# Mock_HASP_Flight_Computer.net
KiCad netlist of a schematic drawn in EAGLE
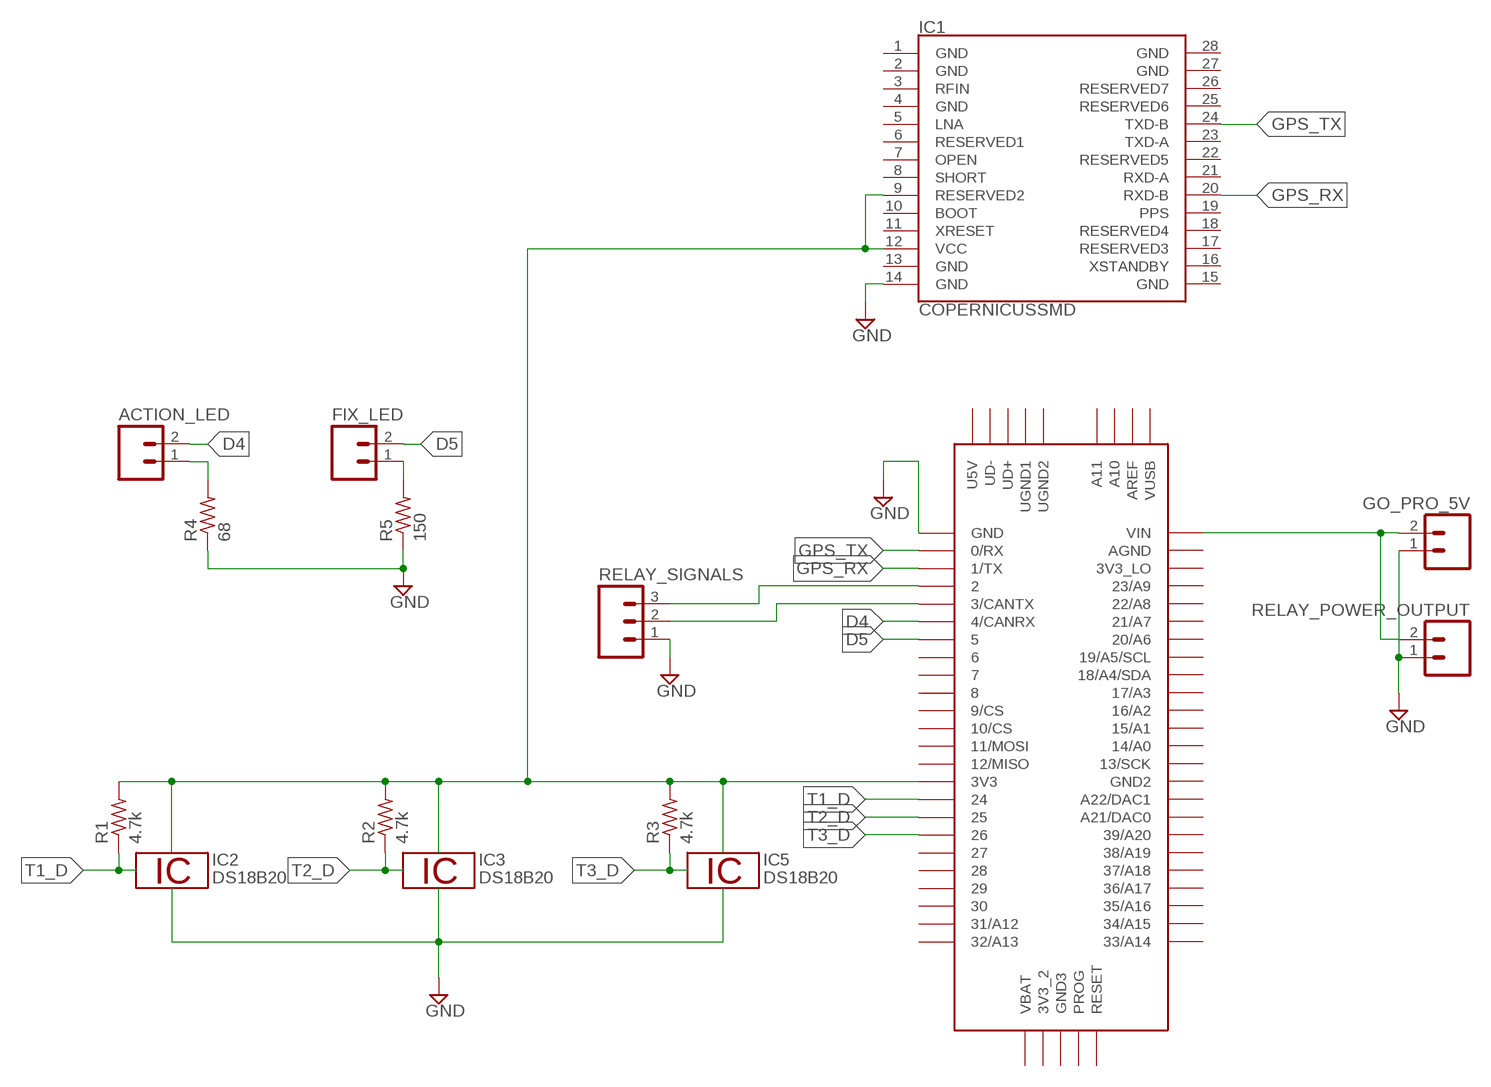
[diagram p0: schematic, sheet 1]

(export (version "E")
  (design (tool "Eeschema 10.0.6"))
  (components
    (comp (ref "ACTION_LED")
      (value "M02")
      (footprint "eagle-import:02P")
      (libsource (lib "eagle-import") (part "M02"))
    )
    (comp (ref "FIX_LED")
      (value "M02")
      (footprint "eagle-import:02P")
      (libsource (lib "eagle-import") (part "M02"))
    )
    (comp (ref "GO_PRO_5V")
      (value "M02")
      (footprint "eagle-import:02P")
      (libsource (lib "eagle-import") (part "M02"))
    )
    (comp (ref "IC1")
      (value "COPERNICUSSMD")
      (footprint "eagle-import:COPERNICUS")
      (libsource (lib "eagle-import") (part "COPERNICUSSMD"))
    )
    (comp (ref "IC2")
      (value "DS18B20")
      (footprint "eagle-import:TO92-")
      (libsource (lib "eagle-import") (part "DS18B20"))
    )
    (comp (ref "IC3")
      (value "DS18B20")
      (footprint "eagle-import:TO92-")
      (libsource (lib "eagle-import") (part "DS18B20"))
    )
    (comp (ref "IC5")
      (value "DS18B20")
      (footprint "eagle-import:TO92-")
      (libsource (lib "eagle-import") (part "DS18B20"))
    )
    (comp (ref "R1")
      (value "4.7k")
      (footprint "eagle-import:0207_10")
      (libsource (lib "eagle-import") (part "R-US_0207/10"))
    )
    (comp (ref "R2")
      (value "4.7k")
      (footprint "eagle-import:0207_10")
      (libsource (lib "eagle-import") (part "R-US_0207/10"))
    )
    (comp (ref "R3")
      (value "4.7k")
      (footprint "eagle-import:0207_10")
      (libsource (lib "eagle-import") (part "R-US_0207/10"))
    )
    (comp (ref "R4")
      (value "68")
      (footprint "eagle-import:0207_10")
      (libsource (lib "eagle-import") (part "R-US_0207/10"))
    )
    (comp (ref "R5")
      (value "150")
      (footprint "eagle-import:0207_10")
      (libsource (lib "eagle-import") (part "R-US_0207/10"))
    )
    (comp (ref "RELAY_POWER_OUTPUT")
      (value "M02")
      (footprint "eagle-import:02P")
      (libsource (lib "eagle-import") (part "M02"))
    )
    (comp (ref "RELAY_SIGNALS")
      (value "M03")
      (footprint "eagle-import:03P")
      (libsource (lib "eagle-import") (part "M03"))
    )
    (comp (ref "U$1")
      (value "TEENSY_3.5/3.6")
      (footprint "eagle-import:TEENSY_3.5_3.6")
      (libsource (lib "eagle-import") (part "TEENSY_3.5/3.6"))
    )
  )
  (nets
    (net (code "1") (name "D4") (class "Default")
      (node (ref "ACTION_LED") (pin "2") (pinfunction "2_2") (pintype "passive"))
      (node (ref "U$1") (pin "4/CANRX") (pinfunction "4/CANRX_4/CANRX") (pintype "bidirectional"))
    )
    (net (code "2") (name "D5") (class "Default")
      (node (ref "FIX_LED") (pin "2") (pinfunction "2_2") (pintype "passive"))
      (node (ref "U$1") (pin "5") (pinfunction "5_5") (pintype "bidirectional"))
    )
    (net (code "3") (name "GND") (class "Default")
      (node (ref "GO_PRO_5V") (pin "1") (pinfunction "1_1") (pintype "passive"))
      (node (ref "IC1") (pin "14") (pinfunction "GND_14") (pintype "bidirectional"))
      (node (ref "R4") (pin "1") (pinfunction "1_1") (pintype "passive"))
      (node (ref "R5") (pin "1") (pinfunction "1_1") (pintype "passive"))
      (node (ref "RELAY_POWER_OUTPUT") (pin "1") (pinfunction "1_1") (pintype "passive"))
      (node (ref "RELAY_SIGNALS") (pin "1") (pinfunction "1_1") (pintype "passive"))
      (node (ref "U$1") (pin "GND") (pinfunction "GND_GND") (pintype "bidirectional"))
    )
    (net (code "4") (name "GPS_RX") (class "Default")
      (node (ref "IC1") (pin "20") (pinfunction "RXD-B_20") (pintype "bidirectional"))
      (node (ref "U$1") (pin "1/TX") (pinfunction "1/TX_1/TX") (pintype "bidirectional"))
    )
    (net (code "5") (name "GPS_TX") (class "Default")
      (node (ref "IC1") (pin "24") (pinfunction "TXD-B_24") (pintype "bidirectional"))
      (node (ref "U$1") (pin "0/RX") (pinfunction "0/RX_0/RX") (pintype "bidirectional"))
    )
    (net (code "6") (name "Net-(ACTION_LED-Pad1)") (class "Default")
      (node (ref "ACTION_LED") (pin "1") (pinfunction "1_1") (pintype "passive"))
      (node (ref "R4") (pin "2") (pinfunction "2_2") (pintype "passive"))
    )
    (net (code "7") (name "Net-(FIX_LED-Pad1)") (class "Default")
      (node (ref "FIX_LED") (pin "1") (pinfunction "1_1") (pintype "passive"))
      (node (ref "R5") (pin "2") (pinfunction "2_2") (pintype "passive"))
    )
    (net (code "8") (name "Net-(GO_PRO_5V-Pad2)") (class "Default")
      (node (ref "GO_PRO_5V") (pin "2") (pinfunction "2_2") (pintype "passive"))
      (node (ref "RELAY_POWER_OUTPUT") (pin "2") (pinfunction "2_2") (pintype "passive"))
      (node (ref "U$1") (pin "VIN") (pinfunction "VIN_VIN") (pintype "bidirectional"))
    )
    (net (code "9") (name "Net-(IC1-RESERVED2)") (class "Default")
      (node (ref "IC1") (pin "12") (pinfunction "VCC_12") (pintype "bidirectional"))
      (node (ref "IC1") (pin "9") (pinfunction "RESERVED2_9") (pintype "bidirectional"))
      (node (ref "R1") (pin "2") (pinfunction "2_2") (pintype "passive"))
      (node (ref "R2") (pin "2") (pinfunction "2_2") (pintype "passive"))
      (node (ref "R3") (pin "2") (pinfunction "2_2") (pintype "passive"))
      (node (ref "U$1") (pin "3V3") (pinfunction "3V3_3V3") (pintype "bidirectional"))
    )
    (net (code "10") (name "Net-(RELAY_SIGNALS-Pad2)") (class "Default")
      (node (ref "RELAY_SIGNALS") (pin "2") (pinfunction "2_2") (pintype "passive"))
      (node (ref "U$1") (pin "3/CANTX") (pinfunction "3/CANTX_3/CANTX") (pintype "bidirectional"))
    )
    (net (code "11") (name "Net-(RELAY_SIGNALS-Pad3)") (class "Default")
      (node (ref "RELAY_SIGNALS") (pin "3") (pinfunction "3_3") (pintype "passive"))
      (node (ref "U$1") (pin "2") (pinfunction "2_2") (pintype "bidirectional"))
    )
    (net (code "12") (name "T1_D") (class "Default")
      (node (ref "R1") (pin "1") (pinfunction "1_1") (pintype "passive"))
      (node (ref "U$1") (pin "24") (pinfunction "24_24") (pintype "bidirectional"))
    )
    (net (code "13") (name "T2_D") (class "Default")
      (node (ref "R2") (pin "1") (pinfunction "1_1") (pintype "passive"))
      (node (ref "U$1") (pin "25") (pinfunction "25_25") (pintype "bidirectional"))
    )
    (net (code "14") (name "T3_D") (class "Default")
      (node (ref "R3") (pin "1") (pinfunction "1_1") (pintype "passive"))
      (node (ref "U$1") (pin "26") (pinfunction "26_26") (pintype "bidirectional"))
    )
    (net (code "15") (name "unconnected-(IC1-BOOT-Pad10)") (class "Default")
      (node (ref "IC1") (pin "10") (pinfunction "BOOT_10") (pintype "bidirectional"))
    )
    (net (code "16") (name "unconnected-(IC1-GND-Pad1)") (class "Default")
      (node (ref "IC1") (pin "1") (pinfunction "GND_1") (pintype "bidirectional"))
    )
    (net (code "17") (name "unconnected-(IC1-GND-Pad2)") (class "Default")
      (node (ref "IC1") (pin "2") (pinfunction "GND_2") (pintype "bidirectional"))
    )
    (net (code "18") (name "unconnected-(IC1-GND-Pad4)") (class "Default")
      (node (ref "IC1") (pin "4") (pinfunction "GND_4") (pintype "bidirectional"))
    )
    (net (code "19") (name "unconnected-(IC1-GND-Pad13)") (class "Default")
      (node (ref "IC1") (pin "13") (pinfunction "GND_13") (pintype "bidirectional"))
    )
    (net (code "20") (name "unconnected-(IC1-GND-Pad15)") (class "Default")
      (node (ref "IC1") (pin "15") (pinfunction "GND_15") (pintype "bidirectional"))
    )
    (net (code "21") (name "unconnected-(IC1-GND-Pad27)") (class "Default")
      (node (ref "IC1") (pin "27") (pinfunction "GND_27") (pintype "bidirectional"))
    )
    (net (code "22") (name "unconnected-(IC1-GND-Pad28)") (class "Default")
      (node (ref "IC1") (pin "28") (pinfunction "GND_28") (pintype "bidirectional"))
    )
    (net (code "23") (name "unconnected-(IC1-LNA-Pad5)") (class "Default")
      (node (ref "IC1") (pin "5") (pinfunction "LNA_5") (pintype "bidirectional"))
    )
    (net (code "24") (name "unconnected-(IC1-OPEN-Pad7)") (class "Default")
      (node (ref "IC1") (pin "7") (pinfunction "OPEN_7") (pintype "bidirectional"))
    )
    (net (code "25") (name "unconnected-(IC1-PPS-Pad19)") (class "Default")
      (node (ref "IC1") (pin "19") (pinfunction "PPS_19") (pintype "bidirectional"))
    )
    (net (code "26") (name "unconnected-(IC1-RESERVED1-Pad6)") (class "Default")
      (node (ref "IC1") (pin "6") (pinfunction "RESERVED1_6") (pintype "bidirectional"))
    )
    (net (code "27") (name "unconnected-(IC1-RESERVED3-Pad17)") (class "Default")
      (node (ref "IC1") (pin "17") (pinfunction "RESERVED3_17") (pintype "bidirectional"))
    )
    (net (code "28") (name "unconnected-(IC1-RESERVED4-Pad18)") (class "Default")
      (node (ref "IC1") (pin "18") (pinfunction "RESERVED4_18") (pintype "bidirectional"))
    )
    (net (code "29") (name "unconnected-(IC1-RESERVED5-Pad22)") (class "Default")
      (node (ref "IC1") (pin "22") (pinfunction "RESERVED5_22") (pintype "bidirectional"))
    )
    (net (code "30") (name "unconnected-(IC1-RESERVED6-Pad25)") (class "Default")
      (node (ref "IC1") (pin "25") (pinfunction "RESERVED6_25") (pintype "bidirectional"))
    )
    (net (code "31") (name "unconnected-(IC1-RESERVED7-Pad26)") (class "Default")
      (node (ref "IC1") (pin "26") (pinfunction "RESERVED7_26") (pintype "bidirectional"))
    )
    (net (code "32") (name "unconnected-(IC1-RFIN-Pad3)") (class "Default")
      (node (ref "IC1") (pin "3") (pinfunction "RFIN_3") (pintype "bidirectional"))
    )
    (net (code "33") (name "unconnected-(IC1-RXD-A-Pad21)") (class "Default")
      (node (ref "IC1") (pin "21") (pinfunction "RXD-A_21") (pintype "bidirectional"))
    )
    (net (code "34") (name "unconnected-(IC1-SHORT-Pad8)") (class "Default")
      (node (ref "IC1") (pin "8") (pinfunction "SHORT_8") (pintype "bidirectional"))
    )
    (net (code "35") (name "unconnected-(IC1-TXD-A-Pad23)") (class "Default")
      (node (ref "IC1") (pin "23") (pinfunction "TXD-A_23") (pintype "bidirectional"))
    )
    (net (code "36") (name "unconnected-(IC1-XRESET-Pad11)") (class "Default")
      (node (ref "IC1") (pin "11") (pinfunction "XRESET_11") (pintype "bidirectional"))
    )
    (net (code "37") (name "unconnected-(IC1-XSTANDBY-Pad16)") (class "Default")
      (node (ref "IC1") (pin "16") (pinfunction "XSTANDBY_16") (pintype "bidirectional"))
    )
    (net (code "38") (name "unconnected-(U$1-A21{slash}DAC0-Pad21{slash}DAC0)") (class "Default")
      (node (ref "U$1") (pin "21/DAC0") (pinfunction "A21/DAC0_21/DAC0") (pintype "bidirectional"))
    )
    (net (code "39") (name "unconnected-(U$1-Pad3V3_2)") (class "Default")
      (node (ref "U$1") (pin "3V3_2") (pinfunction "3V3_2_3V3_2") (pintype "bidirectional"))
    )
    (net (code "40") (name "unconnected-(U$1-Pad3V3_LO)") (class "Default")
      (node (ref "U$1") (pin "3V3_LO") (pinfunction "3V3_LO_3V3_LO") (pintype "bidirectional"))
    )
    (net (code "41") (name "unconnected-(U$1-Pad6)") (class "Default")
      (node (ref "U$1") (pin "6") (pinfunction "6_6") (pintype "bidirectional"))
    )
    (net (code "42") (name "unconnected-(U$1-Pad7)") (class "Default")
      (node (ref "U$1") (pin "7") (pinfunction "7_7") (pintype "bidirectional"))
    )
    (net (code "43") (name "unconnected-(U$1-Pad8)") (class "Default")
      (node (ref "U$1") (pin "8") (pinfunction "8_8") (pintype "bidirectional"))
    )
    (net (code "44") (name "unconnected-(U$1-Pad9{slash}CS)") (class "Default")
      (node (ref "U$1") (pin "9/CS") (pinfunction "9/CS_9/CS") (pintype "bidirectional"))
    )
    (net (code "45") (name "unconnected-(U$1-Pad10{slash}CS)") (class "Default")
      (node (ref "U$1") (pin "10/CS") (pinfunction "10/CS_10/CS") (pintype "bidirectional"))
    )
    (net (code "46") (name "unconnected-(U$1-Pad11{slash}MOSI)") (class "Default")
      (node (ref "U$1") (pin "11/MOSI") (pinfunction "11/MOSI_11/MOSI") (pintype "bidirectional"))
    )
    (net (code "47") (name "unconnected-(U$1-Pad12{slash}MISO)") (class "Default")
      (node (ref "U$1") (pin "12/MISO") (pinfunction "12/MISO_12/MISO") (pintype "bidirectional"))
    )
    (net (code "48") (name "unconnected-(U$1-Pad13{slash}SCK)") (class "Default")
      (node (ref "U$1") (pin "13/SCK") (pinfunction "13/SCK_13/SCK") (pintype "bidirectional"))
    )
    (net (code "49") (name "unconnected-(U$1-Pad14{slash}A0)") (class "Default")
      (node (ref "U$1") (pin "14/A0") (pinfunction "14/A0_14/A0") (pintype "bidirectional"))
    )
    (net (code "50") (name "unconnected-(U$1-Pad15{slash}A1)") (class "Default")
      (node (ref "U$1") (pin "15/A1") (pinfunction "15/A1_15/A1") (pintype "bidirectional"))
    )
    (net (code "51") (name "unconnected-(U$1-Pad16{slash}A2)") (class "Default")
      (node (ref "U$1") (pin "16/A2") (pinfunction "16/A2_16/A2") (pintype "bidirectional"))
    )
    (net (code "52") (name "unconnected-(U$1-Pad17{slash}A3)") (class "Default")
      (node (ref "U$1") (pin "17/A3") (pinfunction "17/A3_17/A3") (pintype "bidirectional"))
    )
    (net (code "53") (name "unconnected-(U$1-Pad18{slash}A4{slash}SDA)") (class "Default")
      (node (ref "U$1") (pin "18/A4/SDA") (pinfunction "18/A4/SDA_18/A4/SDA") (pintype "bidirectional"))
    )
    (net (code "54") (name "unconnected-(U$1-Pad19{slash}A5{slash}SCL)") (class "Default")
      (node (ref "U$1") (pin "19/A5/SCL") (pinfunction "19/A5/SCL_19/A5/SCL") (pintype "bidirectional"))
    )
    (net (code "55") (name "unconnected-(U$1-Pad20{slash}A6)") (class "Default")
      (node (ref "U$1") (pin "20/A6") (pinfunction "20/A6_20/A6") (pintype "bidirectional"))
    )
    (net (code "56") (name "unconnected-(U$1-Pad21{slash}A7)") (class "Default")
      (node (ref "U$1") (pin "21/A7") (pinfunction "21/A7_21/A7") (pintype "bidirectional"))
    )
    (net (code "57") (name "unconnected-(U$1-Pad22{slash}A8)") (class "Default")
      (node (ref "U$1") (pin "22/A8") (pinfunction "22/A8_22/A8") (pintype "bidirectional"))
    )
    (net (code "58") (name "unconnected-(U$1-Pad23{slash}A9)") (class "Default")
      (node (ref "U$1") (pin "23/A9") (pinfunction "23/A9_23/A9") (pintype "bidirectional"))
    )
    (net (code "59") (name "unconnected-(U$1-Pad27)") (class "Default")
      (node (ref "U$1") (pin "27") (pinfunction "27_27") (pintype "bidirectional"))
    )
    (net (code "60") (name "unconnected-(U$1-Pad28)") (class "Default")
      (node (ref "U$1") (pin "28") (pinfunction "28_28") (pintype "bidirectional"))
    )
    (net (code "61") (name "unconnected-(U$1-Pad29)") (class "Default")
      (node (ref "U$1") (pin "29") (pinfunction "29_29") (pintype "bidirectional"))
    )
    (net (code "62") (name "unconnected-(U$1-Pad30)") (class "Default")
      (node (ref "U$1") (pin "30") (pinfunction "30_30") (pintype "bidirectional"))
    )
    (net (code "63") (name "unconnected-(U$1-Pad31{slash}A12)") (class "Default")
      (node (ref "U$1") (pin "31/A12") (pinfunction "31/A12_31/A12") (pintype "bidirectional"))
    )
    (net (code "64") (name "unconnected-(U$1-Pad32{slash}A13)") (class "Default")
      (node (ref "U$1") (pin "32/A13") (pinfunction "32/A13_32/A13") (pintype "bidirectional"))
    )
    (net (code "65") (name "unconnected-(U$1-Pad33{slash}A14)") (class "Default")
      (node (ref "U$1") (pin "33/A14") (pinfunction "33/A14_33/A14") (pintype "bidirectional"))
    )
    (net (code "66") (name "unconnected-(U$1-Pad34{slash}A15)") (class "Default")
      (node (ref "U$1") (pin "34/A15") (pinfunction "34/A15_34/A15") (pintype "bidirectional"))
    )
    (net (code "67") (name "unconnected-(U$1-Pad35{slash}A16)") (class "Default")
      (node (ref "U$1") (pin "35/A16") (pinfunction "35/A16_35/A16") (pintype "bidirectional"))
    )
    (net (code "68") (name "unconnected-(U$1-Pad36{slash}A17)") (class "Default")
      (node (ref "U$1") (pin "36/A17") (pinfunction "36/A17_36/A17") (pintype "bidirectional"))
    )
    (net (code "69") (name "unconnected-(U$1-Pad37{slash}A18)") (class "Default")
      (node (ref "U$1") (pin "37/A18") (pinfunction "37/A18_37/A18") (pintype "bidirectional"))
    )
    (net (code "70") (name "unconnected-(U$1-Pad38{slash}A19)") (class "Default")
      (node (ref "U$1") (pin "38/A19") (pinfunction "38/A19_38/A19") (pintype "bidirectional"))
    )
    (net (code "71") (name "unconnected-(U$1-Pad39{slash}A20)") (class "Default")
      (node (ref "U$1") (pin "39/A20") (pinfunction "39/A20_39/A20") (pintype "bidirectional"))
    )
    (net (code "72") (name "unconnected-(U$1-PadA10)") (class "Default")
      (node (ref "U$1") (pin "A10") (pinfunction "A10_A10") (pintype "bidirectional"))
    )
    (net (code "73") (name "unconnected-(U$1-PadA11)") (class "Default")
      (node (ref "U$1") (pin "A11") (pinfunction "A11_A11") (pintype "bidirectional"))
    )
    (net (code "74") (name "unconnected-(U$1-PadA22{slash}DAC1)") (class "Default")
      (node (ref "U$1") (pin "A22/DAC1") (pinfunction "A22/DAC1_A22/DAC1") (pintype "bidirectional"))
    )
    (net (code "75") (name "unconnected-(U$1-PadAGND)") (class "Default")
      (node (ref "U$1") (pin "AGND") (pinfunction "AGND_AGND") (pintype "bidirectional"))
    )
    (net (code "76") (name "unconnected-(U$1-PadAREF)") (class "Default")
      (node (ref "U$1") (pin "AREF") (pinfunction "AREF_AREF") (pintype "bidirectional"))
    )
    (net (code "77") (name "unconnected-(U$1-PadGND2)") (class "Default")
      (node (ref "U$1") (pin "GND2") (pinfunction "GND2_GND2") (pintype "bidirectional"))
    )
    (net (code "78") (name "unconnected-(U$1-PadGND3)") (class "Default")
      (node (ref "U$1") (pin "GND3") (pinfunction "GND3_GND3") (pintype "bidirectional"))
    )
    (net (code "79") (name "unconnected-(U$1-PadPROG)") (class "Default")
      (node (ref "U$1") (pin "PROG") (pinfunction "PROG_PROG") (pintype "bidirectional"))
    )
    (net (code "80") (name "unconnected-(U$1-PadRESET)") (class "Default")
      (node (ref "U$1") (pin "RESET") (pinfunction "RESET_RESET") (pintype "bidirectional"))
    )
    (net (code "81") (name "unconnected-(U$1-PadU5V)") (class "Default")
      (node (ref "U$1") (pin "U5V") (pinfunction "U5V_U5V") (pintype "bidirectional"))
    )
    (net (code "82") (name "unconnected-(U$1-PadUD+)") (class "Default")
      (node (ref "U$1") (pin "UD+") (pinfunction "UD+_UD+") (pintype "bidirectional"))
    )
    (net (code "83") (name "unconnected-(U$1-PadUD-)") (class "Default")
      (node (ref "U$1") (pin "UD-") (pinfunction "UD-_UD-") (pintype "bidirectional"))
    )
    (net (code "84") (name "unconnected-(U$1-PadUGND1)") (class "Default")
      (node (ref "U$1") (pin "UGND1") (pinfunction "UGND1_UGND1") (pintype "bidirectional"))
    )
    (net (code "85") (name "unconnected-(U$1-PadUGND2)") (class "Default")
      (node (ref "U$1") (pin "UGND2") (pinfunction "UGND2_UGND2") (pintype "bidirectional"))
    )
    (net (code "86") (name "unconnected-(U$1-PadVBAT)") (class "Default")
      (node (ref "U$1") (pin "VBAT") (pinfunction "VBAT_VBAT") (pintype "bidirectional"))
    )
    (net (code "87") (name "unconnected-(U$1-PadVUSB)") (class "Default")
      (node (ref "U$1") (pin "VUSB") (pinfunction "VUSB_VUSB") (pintype "bidirectional"))
    )
  )
)
